# nanoDAP-mini.net
KiCad netlist of a schematic drawn in Altium Designer
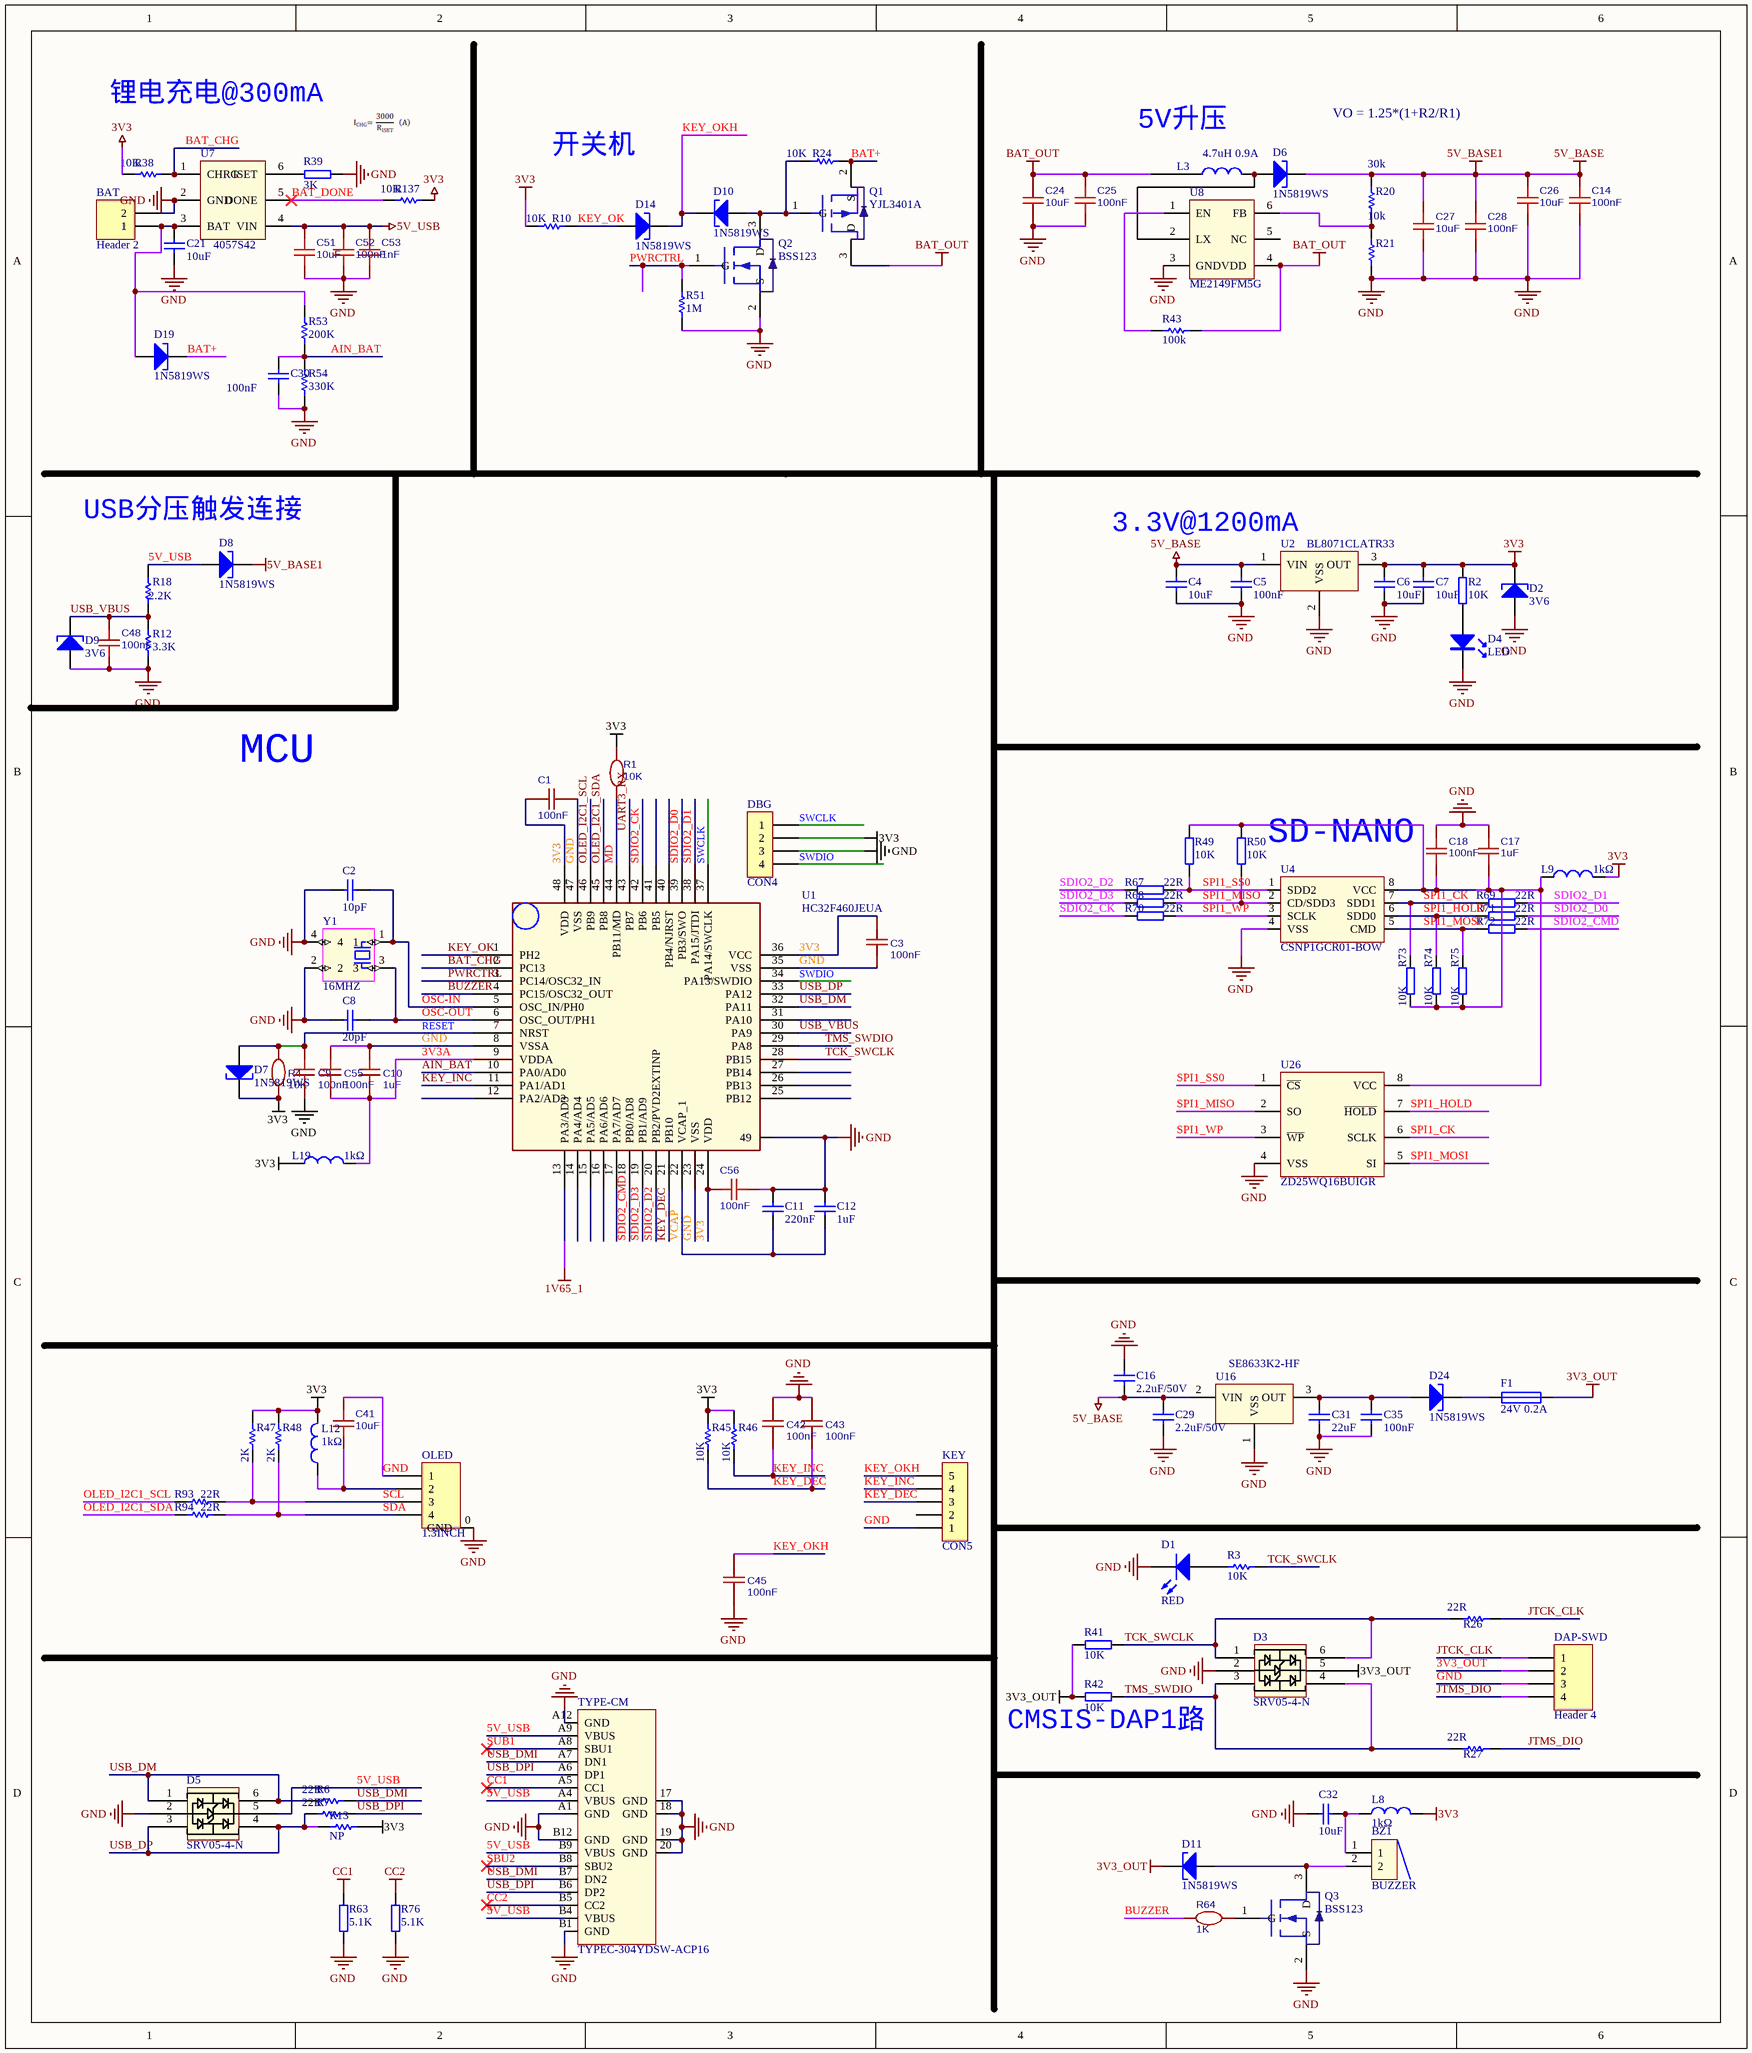
[diagram p0: nanoDAP-mini.SchDoc]

(export (version "E")
  (design (tool "Eeschema 10.0.6"))
  (components
    (comp (ref "BAT")
      (value "Header 2")
      (footprint "XH2.54-2P")
      (description "Header, 2-Pin")
      (fields (field (name "PUBLISHER") "Altium Limited"))
      (libsource (lib "Miscellaneous Connectors") (part "Header 2"))
    )
    (comp (ref "BZ1")
      (value "BUZZER")
      (footprint "BUZ-TH_BD9.0-P5.00-D0.6-FD")
      (libsource (lib "Schlib") (part "BUZZER"))
    )
    (comp (ref "C1")
      (value "100nF")
      (footprint "C0603")
      (libsource (lib "altium-import") (part "root_1_100nF_"))
    )
    (comp (ref "C2")
      (value "10pF")
      (footprint "C0603")
      (description "Capacitor")
      (fields (field (name "PUBLISHER") "Altium Limited"))
      (libsource (lib "Miscellaneous Devices") (part "Cap"))
    )
    (comp (ref "C3")
      (value "100nF")
      (footprint "C0603")
      (libsource (lib "altium-import") (part "root_0_100nF_"))
    )
    (comp (ref "C4")
      (value "10uF")
      (footprint "PcbLib:C0603")
      (description "电容")
      (libsource (lib "") (part "Cap2_1"))
    )
    (comp (ref "C5")
      (value "100nF")
      (footprint "PcbLib:C0603")
      (description "电容")
      (libsource (lib "") (part "Cap2_1"))
    )
    (comp (ref "C6")
      (value "10uF")
      (footprint "C0603")
      (description "电容")
      (libsource (lib "") (part "Cap2_1"))
    )
    (comp (ref "C7")
      (value "10uF")
      (footprint "C0603")
      (description "电容")
      (libsource (lib "Schlib") (part "Cap2"))
    )
    (comp (ref "C8")
      (value "20pF")
      (footprint "C0603")
      (description "Capacitor")
      (fields (field (name "PUBLISHER") "Altium Limited"))
      (libsource (lib "Miscellaneous Devices") (part "Cap"))
    )
    (comp (ref "C9")
      (value "100nF")
      (footprint "C0603")
      (libsource (lib "altium-import") (part "root_0_100nF_"))
    )
    (comp (ref "C10")
      (value "1uF")
      (footprint "C0603")
      (libsource (lib "altium-import") (part "root_0_100nF_"))
    )
    (comp (ref "C11")
      (value "220nF")
      (footprint "C0603")
      (description "Capacitor")
      (fields (field (name "PUBLISHER") "Altium Limited"))
      (libsource (lib "Miscellaneous Devices") (part "Cap"))
    )
    (comp (ref "C12")
      (value "1uF")
      (footprint "C0603")
      (description "Capacitor")
      (fields (field (name "PUBLISHER") "Altium Limited"))
      (libsource (lib "Miscellaneous Devices") (part "Cap"))
    )
    (comp (ref "C14")
      (value "100nF")
      (footprint "C0603")
      (libsource (lib "altium-import") (part "root_2_100nF_"))
    )
    (comp (ref "C16")
      (value "2.2uF/50V")
      (footprint "C0805")
      (description "电容")
      (libsource (lib "Schlib") (part "Cap2"))
    )
    (comp (ref "C17")
      (value "1uF")
      (footprint "C0603")
      (libsource (lib "altium-import") (part "root_0_100nF_"))
    )
    (comp (ref "C18")
      (value "100nF")
      (footprint "C0603")
      (libsource (lib "altium-import") (part "root_0_100nF_"))
    )
    (comp (ref "C21")
      (value "10uF")
      (footprint "C0603")
      (description "电容")
      (libsource (lib "Schlib") (part "Cap2"))
    )
    (comp (ref "C24")
      (value "10uF")
      (footprint "C0603")
      (libsource (lib "altium-import") (part "root_2_100nF_"))
    )
    (comp (ref "C25")
      (value "100nF")
      (footprint "C0603")
      (libsource (lib "altium-import") (part "root_2_100nF_"))
    )
    (comp (ref "C26")
      (value "10uF")
      (footprint "C0603")
      (libsource (lib "altium-import") (part "root_2_100nF_"))
    )
    (comp (ref "C27")
      (value "10uF")
      (footprint "C0603")
      (libsource (lib "altium-import") (part "root_2_100nF_"))
    )
    (comp (ref "C28")
      (value "100nF")
      (footprint "C0603")
      (libsource (lib "altium-import") (part "root_2_100nF_"))
    )
    (comp (ref "C29")
      (value "2.2uF/50V")
      (footprint "C0805")
      (description "电容")
      (libsource (lib "") (part "Cap2_1"))
    )
    (comp (ref "C30")
      (value "100nF")
      (footprint "C0603")
      (description "电容")
      (libsource (lib "Schlib") (part "Cap2"))
    )
    (comp (ref "C31")
      (value "22uF")
      (footprint "C0805")
      (description "电容")
      (libsource (lib "") (part "Cap2_1"))
    )
    (comp (ref "C32")
      (value "10uF")
      (footprint "C0603")
      (description "电容")
      (libsource (lib "Schlib") (part "Cap2"))
    )
    (comp (ref "C35")
      (value "100nF")
      (footprint "C0805")
      (description "电容")
      (libsource (lib "") (part "Cap2_1"))
    )
    (comp (ref "C41")
      (value "10uF")
      (footprint "C0603")
      (libsource (lib "altium-import") (part "root_2_100nF_"))
    )
    (comp (ref "C42")
      (value "100nF")
      (footprint "C0603")
      (libsource (lib "altium-import") (part "root_0_100nF_"))
    )
    (comp (ref "C43")
      (value "100nF")
      (footprint "C0603")
      (libsource (lib "altium-import") (part "root_0_100nF_"))
    )
    (comp (ref "C45")
      (value "100nF")
      (footprint "C0603")
      (libsource (lib "altium-import") (part "root_0_100nF_"))
    )
    (comp (ref "C48")
      (value "100nF")
      (footprint "C0603")
      (libsource (lib "altium-import") (part "root_0_100nF_"))
    )
    (comp (ref "C51")
      (value "10uF")
      (footprint "C0603")
      (libsource (lib "altium-import") (part "root_2_100nF_"))
    )
    (comp (ref "C52")
      (value "100nF")
      (footprint "C0603")
      (libsource (lib "altium-import") (part "root_2_100nF_"))
    )
    (comp (ref "C53")
      (value "1nF")
      (footprint "C0603")
      (libsource (lib "altium-import") (part "root_2_100nF_"))
    )
    (comp (ref "C55")
      (value "100nF")
      (footprint "C0603")
      (libsource (lib "altium-import") (part "root_0_100nF_"))
    )
    (comp (ref "C56")
      (value "100nF")
      (footprint "C0603")
      (libsource (lib "altium-import") (part "root_1_100nF_"))
    )
    (comp (ref "D1")
      (value "RED")
      (footprint "0603_LED")
      (description "Typical RED, GREEN, YELLOW, AMBER GaAs LED")
      (fields (field (name "PUBLISHER") "Altium Limited"))
      (libsource (lib "MYLIB") (part "D0603"))
    )
    (comp (ref "D2")
      (value "3V6")
      (footprint "LL-34")
      (description "稳压二极管")
      (fields (field (name "PUBLISHER") "Altium Limited"))
      (libsource (lib "Schlib") (part "Diode Zener"))
    )
    (comp (ref "D3") (value "SRV05-4-N") (footprint "SOT-23-6") (libsource (lib "Schlib") (part "ESD-USB")))
    (comp (ref "D4") (value "LED") (footprint "PcbLib:0603_LED") (libsource (lib "Schlib") (part "LED")))
    (comp (ref "D5") (value "SRV05-4-N") (footprint "SOT-23-6") (libsource (lib "Schlib") (part "ESD-USB")))
    (comp (ref "D6")
      (value "1N5819WS")
      (footprint "SOD-323")
      (description "稳压二极管")
      (fields (field (name "PUBLISHER") "Altium Limited"))
      (libsource (lib "Schlib") (part "Diode Zener"))
    )
    (comp (ref "D7")
      (value "1N5819WS")
      (footprint "SOD-323")
      (description "稳压二极管")
      (fields (field (name "PUBLISHER") "Altium Limited"))
      (libsource (lib "Schlib") (part "Diode Zener"))
    )
    (comp (ref "D8")
      (value "1N5819WS")
      (footprint "SOD-323")
      (description "稳压二极管")
      (fields (field (name "PUBLISHER") "Altium Limited"))
      (libsource (lib "Schlib") (part "Diode Zener"))
    )
    (comp (ref "D9")
      (value "3V6")
      (footprint "SOD-323")
      (description "稳压二极管")
      (fields (field (name "PUBLISHER") "Altium Limited"))
      (libsource (lib "Schlib") (part "Diode Zener"))
    )
    (comp (ref "D10")
      (value "1N5819WS")
      (footprint "SOD-323")
      (description "稳压二极管")
      (fields (field (name "PUBLISHER") "Altium Limited"))
      (libsource (lib "Schlib") (part "Diode Zener"))
    )
    (comp (ref "D11")
      (value "1N5819WS")
      (footprint "SOD-323")
      (description "稳压二极管")
      (fields (field (name "PUBLISHER") "Altium Limited"))
      (libsource (lib "Schlib") (part "Diode Zener"))
    )
    (comp (ref "D14")
      (value "1N5819WS")
      (footprint "SOD-323")
      (description "稳压二极管")
      (fields (field (name "PUBLISHER") "Altium Limited"))
      (libsource (lib "Schlib") (part "Diode Zener"))
    )
    (comp (ref "D19")
      (value "1N5819WS")
      (footprint "SOD-323")
      (description "稳压二极管")
      (fields (field (name "PUBLISHER") "Altium Limited"))
      (libsource (lib "Schlib") (part "Diode Zener"))
    )
    (comp (ref "D24")
      (value "1N5819WS")
      (footprint "SOD-323")
      (description "稳压二极管")
      (fields (field (name "PUBLISHER") "Altium Limited"))
      (libsource (lib "Schlib") (part "Diode Zener"))
    )
    (comp (ref "DAP-SWD")
      (value "Header 4")
      (footprint "XH2.54-4P")
      (description "Header, 4-Pin")
      (fields (field (name "PUBLISHER") "Altium Limited"))
      (libsource (lib "Miscellaneous Connectors") (part "Header 4"))
    )
    (comp (ref "DBG")
      (value "CON4")
      (footprint "PcbLib:HDR1X4-SWD")
      (description "连接器")
      (libsource (lib "Schlib") (part "CON4"))
    )
    (comp (ref "F1")
      (value "24V 0.2A")
      (footprint "R0805")
      (description "保险丝")
      (libsource (lib "Schlib") (part "FUSE"))
    )
    (comp (ref "KEY")
      (value "CON5")
      (footprint "HDR1X5")
      (description "连接器")
      (libsource (lib "Schlib") (part "CON5"))
    )
    (comp (ref "L3")
      (value "4.7uH 0.9A")
      (footprint "IND_3x3")
      (description "电感")
      (libsource (lib "Schlib") (part "Inductor"))
    )
    (comp (ref "L8")
      (value "1kΩ")
      (footprint "L0603")
      (description "电感")
      (libsource (lib "Schlib") (part "Inductor"))
    )
    (comp (ref "L9")
      (value "1kΩ")
      (footprint "L0603")
      (description "电感")
      (libsource (lib "Schlib") (part "Inductor"))
    )
    (comp (ref "L12")
      (value "1kΩ")
      (footprint "L0603")
      (description "电感")
      (libsource (lib "Schlib") (part "Inductor"))
    )
    (comp (ref "L19")
      (value "1kΩ")
      (footprint "L0603")
      (description "电感")
      (libsource (lib "Schlib") (part "Inductor"))
    )
    (comp (ref "OLED")
      (value "1.3INCH")
      (footprint "OLED-4p-1.3inch-i2c")
      (description "Header, 4-Pin")
      (fields (field (name "PUBLISHER") "Altium Limited"))
      (libsource (lib "") (part "Header 4_1"))
    )
    (comp (ref "Q1")
      (value "YJL3401A")
      (footprint "PcbLib:SOT-23(SOT-23-3)")
      (description "PMOS")
      (libsource (lib "Schlib") (part "PMOS"))
    )
    (comp (ref "Q2")
      (value "BSS123")
      (footprint "SOT-23(SOT-23-3)")
      (description "NMOS")
      (libsource (lib "Schlib") (part "NMOS"))
    )
    (comp (ref "Q3")
      (value "BSS123")
      (footprint "SOT-23(SOT-23-3)")
      (description "NMOS")
      (libsource (lib "Schlib") (part "NMOS"))
    )
    (comp (ref "R1") (value "10K") (footprint "R0603") (libsource (lib "altium-import") (part "root_3_10K_")))
    (comp (ref "R2")
      (value "10K")
      (footprint "R0603")
      (description "电阻")
      (libsource (lib "Schlib") (part "RES"))
    )
    (comp (ref "R3")
      (value "10K")
      (footprint "R0603")
      (description "Resistor")
      (fields (field (name "PUBLISHER") "Altium Limited"))
      (libsource (lib "MYLIB") (part "0603-1"))
    )
    (comp (ref "R4") (value "10K") (footprint "R0603") (libsource (lib "altium-import") (part "root_1_10K_")))
    (comp (ref "R6")
      (value "22R")
      (footprint "R0603")
      (description "Resistor")
      (fields (field (name "PUBLISHER") "Altium Limited"))
      (libsource (lib "MYLIB") (part "0603-1"))
    )
    (comp (ref "R7")
      (value "22R")
      (footprint "R0603")
      (description "Resistor")
      (fields (field (name "PUBLISHER") "Altium Limited"))
      (libsource (lib "MYLIB") (part "0603-1"))
    )
    (comp (ref "R10")
      (value "10K")
      (footprint "R0603")
      (description "Resistor")
      (fields (field (name "PUBLISHER") "Altium Limited"))
      (libsource (lib "MYLIB") (part "0603-1"))
    )
    (comp (ref "R12")
      (value "3.3K")
      (footprint "R0603")
      (description "Resistor")
      (fields (field (name "PUBLISHER") "Altium Limited"))
      (libsource (lib "MYLIB") (part "0603-1"))
    )
    (comp (ref "R13")
      (value "NP")
      (footprint "R0603")
      (description "Resistor")
      (fields (field (name "PUBLISHER") "Altium Limited"))
      (libsource (lib "MYLIB") (part "0603-1"))
    )
    (comp (ref "R18")
      (value "2.2K")
      (footprint "R0603")
      (description "Resistor")
      (fields (field (name "PUBLISHER") "Altium Limited"))
      (libsource (lib "MYLIB") (part "0603-1"))
    )
    (comp (ref "R20")
      (value "30k")
      (footprint "R0603")
      (description "Resistor")
      (fields (field (name "PUBLISHER") "Altium Limited"))
      (libsource (lib "MYLIB") (part "0603-1"))
    )
    (comp (ref "R21")
      (value "10k")
      (footprint "R0603")
      (description "Resistor")
      (fields (field (name "PUBLISHER") "Altium Limited"))
      (libsource (lib "MYLIB") (part "0603-1"))
    )
    (comp (ref "R24")
      (value "10K")
      (footprint "R0603")
      (description "Resistor")
      (fields (field (name "PUBLISHER") "Altium Limited"))
      (libsource (lib "MYLIB") (part "0603-1"))
    )
    (comp (ref "R26")
      (value "22R")
      (footprint "R0603")
      (description "Resistor")
      (fields (field (name "PUBLISHER") "Altium Limited"))
      (libsource (lib "MYLIB") (part "0603-1"))
    )
    (comp (ref "R27")
      (value "22R")
      (footprint "R0603")
      (description "Resistor")
      (fields (field (name "PUBLISHER") "Altium Limited"))
      (libsource (lib "MYLIB") (part "0603-1"))
    )
    (comp (ref "R38")
      (value "10K")
      (footprint "R0603")
      (description "Resistor")
      (fields (field (name "PUBLISHER") "Altium Limited"))
      (libsource (lib "MYLIB") (part "0603-1"))
    )
    (comp (ref "R39")
      (value "3K")
      (footprint "R0603")
      (description "电阻")
      (libsource (lib "Schlib") (part "RES"))
    )
    (comp (ref "R41")
      (value "10K")
      (footprint "R0603")
      (description "电阻")
      (libsource (lib "Schlib") (part "RES"))
    )
    (comp (ref "R42")
      (value "10K")
      (footprint "R0603")
      (description "电阻")
      (libsource (lib "Schlib") (part "RES"))
    )
    (comp (ref "R43")
      (value "100k")
      (footprint "R0603")
      (description "Resistor")
      (fields (field (name "PUBLISHER") "Altium Limited"))
      (libsource (lib "MYLIB") (part "0603-1"))
    )
    (comp (ref "R45")
      (value "10K")
      (footprint "R0603")
      (description "Resistor")
      (fields (field (name "PUBLISHER") "Altium Limited"))
      (libsource (lib "MYLIB") (part "0603-1"))
    )
    (comp (ref "R46")
      (value "10K")
      (footprint "R0603")
      (description "Resistor")
      (fields (field (name "PUBLISHER") "Altium Limited"))
      (libsource (lib "MYLIB") (part "0603-1"))
    )
    (comp (ref "R47")
      (value "2K")
      (footprint "R0603")
      (description "Resistor")
      (fields (field (name "PUBLISHER") "Altium Limited"))
      (libsource (lib "MYLIB") (part "0603-1"))
    )
    (comp (ref "R48")
      (value "2K")
      (footprint "R0603")
      (description "Resistor")
      (fields (field (name "PUBLISHER") "Altium Limited"))
      (libsource (lib "MYLIB") (part "0603-1"))
    )
    (comp (ref "R49")
      (value "10K")
      (footprint "R0603")
      (description "电阻")
      (libsource (lib "Schlib") (part "RES"))
    )
    (comp (ref "R50")
      (value "10K")
      (footprint "R0603")
      (description "电阻")
      (libsource (lib "Schlib") (part "RES"))
    )
    (comp (ref "R51")
      (value "1M")
      (footprint "R0603")
      (description "Resistor")
      (fields (field (name "PUBLISHER") "Altium Limited"))
      (libsource (lib "MYLIB") (part "0603-1"))
    )
    (comp (ref "R53")
      (value "200K")
      (footprint "R0603")
      (description "Resistor")
      (fields (field (name "PUBLISHER") "Altium Limited"))
      (libsource (lib "MYLIB") (part "0603-1"))
    )
    (comp (ref "R54")
      (value "330K")
      (footprint "R0603")
      (description "Resistor")
      (fields (field (name "PUBLISHER") "Altium Limited"))
      (libsource (lib "MYLIB") (part "0603-1"))
    )
    (comp (ref "R63")
      (value "5.1K")
      (footprint "R0603")
      (description "电阻")
      (libsource (lib "") (part "RES_1"))
    )
    (comp (ref "R64") (value "1K") (footprint "R0603") (libsource (lib "altium-import") (part "root_0_10K_")))
    (comp (ref "R67")
      (value "22R")
      (footprint "R0603")
      (description "电阻")
      (libsource (lib "Schlib") (part "RES"))
    )
    (comp (ref "R68")
      (value "22R")
      (footprint "R0603")
      (description "电阻")
      (libsource (lib "Schlib") (part "RES"))
    )
    (comp (ref "R69")
      (value "22R")
      (footprint "R0603")
      (description "电阻")
      (libsource (lib "Schlib") (part "RES"))
    )
    (comp (ref "R70")
      (value "22R")
      (footprint "R0603")
      (description "电阻")
      (libsource (lib "Schlib") (part "RES"))
    )
    (comp (ref "R71")
      (value "22R")
      (footprint "R0603")
      (description "电阻")
      (libsource (lib "Schlib") (part "RES"))
    )
    (comp (ref "R72")
      (value "22R")
      (footprint "R0603")
      (description "电阻")
      (libsource (lib "Schlib") (part "RES"))
    )
    (comp (ref "R73")
      (value "10K")
      (footprint "R0603")
      (description "电阻")
      (libsource (lib "Schlib") (part "RES"))
    )
    (comp (ref "R74")
      (value "10K")
      (footprint "R0603")
      (description "电阻")
      (libsource (lib "Schlib") (part "RES"))
    )
    (comp (ref "R75")
      (value "10K")
      (footprint "R0603")
      (description "电阻")
      (libsource (lib "Schlib") (part "RES"))
    )
    (comp (ref "R76")
      (value "5.1K")
      (footprint "R0603")
      (description "电阻")
      (libsource (lib "") (part "RES_1"))
    )
    (comp (ref "R93")
      (value "22R")
      (footprint "R0603")
      (description "Resistor")
      (fields (field (name "PUBLISHER") "Altium Limited"))
      (libsource (lib "MYLIB") (part "0603-1"))
    )
    (comp (ref "R94")
      (value "22R")
      (footprint "R0603")
      (description "Resistor")
      (fields (field (name "PUBLISHER") "Altium Limited"))
      (libsource (lib "MYLIB") (part "0603-1"))
    )
    (comp (ref "R137")
      (value "10K")
      (footprint "R0603")
      (description "Resistor")
      (fields (field (name "PUBLISHER") "Altium Limited"))
      (libsource (lib "MYLIB") (part "0603-1"))
    )
    (comp (ref "TYPE-CM")
      (value "TYPEC-304YDSW-ACP16")
      (footprint "USB-C-SMD_TYPEC-304YDSW-ACP16")
      (libsource (lib "Schlib") (part "USB-TYPE-C-母"))
    )
    (comp (ref "U1")
      (value "HC32F460JEUA")
      (footprint "QFN-48_5X5X035P")
      (libsource (lib "Schlib") (part "LQFP48"))
    )
    (comp (ref "U2") (value "BL8071CLATR33") (footprint "SOT-223") (libsource (lib "Schlib") (part "LDO")))
    (comp (ref "U4")
      (value "CSNP1GCR01-BOW")
      (footprint "LGA-8_L6.0-W8.0-P1.27-TL")
      (libsource (lib "Schlib") (part "SD-NAND-SMD"))
    )
    (comp (ref "U7") (value "4057S42") (footprint "SOT-23-6") (libsource (lib "Schlib") (part "IC_6")))
    (comp (ref "U8") (value "ME2149FM5G") (footprint "SOT-23-6") (libsource (lib "Schlib") (part "IC_6")))
    (comp (ref "U16") (value "SE8633K2-HF") (footprint "SOT-89&SOT-23") (libsource (lib "") (part "LDO_1")))
    (comp (ref "U26")
      (value "ZD25WQ16BUIGR")
      (footprint "USON-8_L3.0-W2.0-P0.50-BL-EP_ZD25XX")
      (libsource (lib "Schlib") (part "IC_8"))
    )
    (comp (ref "Y1")
      (value "16MHZ")
      (footprint "SMD-3225_4P")
      (libsource (lib "我的元件库") (part "crystal_smd_3225"))
    )
  )
  (nets
    (net (code "1") (name "/3V3A") (class "Default")
      (node (ref "C10") (pin "1") (pinfunction "1_1") (pintype "passive"))
      (node (ref "C55") (pin "1") (pinfunction "1_1") (pintype "passive"))
      (node (ref "L19") (pin "2") (pinfunction "2_2") (pintype "passive"))
      (node (ref "U1") (pin "9") (pinfunction "VDDA_9") (pintype "passive"))
    )
    (net (code "2") (name "/AIN_BAT") (class "Default")
      (node (ref "C30") (pin "1") (pinfunction "1_1") (pintype "passive"))
      (node (ref "R53") (pin "2") (pinfunction "2_2") (pintype "passive"))
      (node (ref "R54") (pin "2") (pinfunction "2_2") (pintype "passive"))
      (node (ref "U1") (pin "10") (pinfunction "PA0/AD0_10") (pintype "passive"))
    )
    (net (code "3") (name "/BAT+") (class "Default")
      (node (ref "D19") (pin "2") (pinfunction "K_2") (pintype "passive"))
      (node (ref "Q1") (pin "2") (pinfunction "S_2") (pintype "passive"))
      (node (ref "R24") (pin "1") (pinfunction "1_1") (pintype "passive"))
    )
    (net (code "4") (name "/BAT_CHG") (class "Default")
      (node (ref "R38") (pin "1") (pinfunction "1_1") (pintype "passive"))
      (node (ref "U1") (pin "2") (pinfunction "PC13_2") (pintype "passive"))
      (node (ref "U7") (pin "1") (pinfunction "CHRG_1") (pintype "passive"))
    )
    (net (code "5") (name "/BAT_DONE") (class "Default")
      (node (ref "R137") (pin "2") (pinfunction "2_2") (pintype "passive"))
      (node (ref "U7") (pin "5") (pinfunction "DONE_5") (pintype "passive"))
    )
    (net (code "6") (name "/BUZZER") (class "Default")
      (node (ref "R64") (pin "1") (pinfunction "1_1") (pintype "passive"))
      (node (ref "U1") (pin "4") (pinfunction "PC15/OSC32_OUT_4") (pintype "passive"))
    )
    (net (code "7") (name "/JTCK_CLK") (class "Default")
      (node (ref "DAP-SWD") (pin "1") (pinfunction "1_1") (pintype "passive"))
      (node (ref "R26") (pin "2") (pinfunction "2_2") (pintype "passive"))
    )
    (net (code "8") (name "/JTMS_DIO") (class "Default")
      (node (ref "DAP-SWD") (pin "4") (pinfunction "4_4") (pintype "passive"))
      (node (ref "R27") (pin "2") (pinfunction "2_2") (pintype "passive"))
    )
    (net (code "9") (name "/KEY_DEC") (class "Default")
      (node (ref "C43") (pin "1") (pinfunction "1_1") (pintype "passive"))
      (node (ref "KEY") (pin "3") (pinfunction "3_3") (pintype "passive"))
      (node (ref "R45") (pin "2") (pinfunction "2_2") (pintype "passive"))
      (node (ref "U1") (pin "21") (pinfunction "PB10_21") (pintype "passive"))
    )
    (net (code "10") (name "/KEY_INC") (class "Default")
      (node (ref "C42") (pin "1") (pinfunction "1_1") (pintype "passive"))
      (node (ref "KEY") (pin "4") (pinfunction "4_4") (pintype "passive"))
      (node (ref "R46") (pin "2") (pinfunction "2_2") (pintype "passive"))
      (node (ref "U1") (pin "11") (pinfunction "PA1/AD1_11") (pintype "passive"))
    )
    (net (code "11") (name "/KEY_OK") (class "Default")
      (node (ref "D14") (pin "1") (pinfunction "A_1") (pintype "passive"))
      (node (ref "R10") (pin "2") (pinfunction "2_2") (pintype "passive"))
      (node (ref "U1") (pin "1") (pinfunction "PH2_1") (pintype "passive"))
    )
    (net (code "12") (name "/KEY_OKH") (class "Default")
      (node (ref "C45") (pin "2") (pinfunction "2_2") (pintype "passive"))
      (node (ref "D10") (pin "2") (pinfunction "K_2") (pintype "passive"))
      (node (ref "D14") (pin "2") (pinfunction "K_2") (pintype "passive"))
      (node (ref "KEY") (pin "5") (pinfunction "5_5") (pintype "passive"))
    )
    (net (code "13") (name "/MD") (class "Default")
      (node (ref "R1") (pin "2") (pinfunction "2_2") (pintype "passive"))
      (node (ref "U1") (pin "44") (pinfunction "PB11/MD_44") (pintype "passive"))
    )
    (net (code "14") (name "/OLED_I2C1_SCL") (class "Default")
      (node (ref "R93") (pin "1") (pinfunction "1_1") (pintype "passive"))
      (node (ref "U1") (pin "46") (pinfunction "PB9_46") (pintype "passive"))
    )
    (net (code "15") (name "/OLED_I2C1_SDA") (class "Default")
      (node (ref "R94") (pin "1") (pinfunction "1_1") (pintype "passive"))
      (node (ref "U1") (pin "45") (pinfunction "PB8_45") (pintype "passive"))
    )
    (net (code "16") (name "/OSC-IN") (class "Default")
      (node (ref "C2") (pin "2") (pinfunction "2_2") (pintype "passive"))
      (node (ref "U1") (pin "5") (pinfunction "OSC_IN/PH0_5") (pintype "passive"))
      (node (ref "Y1") (pin "1") (pinfunction "1_1") (pintype "bidirectional"))
    )
    (net (code "17") (name "/OSC-OUT") (class "Default")
      (node (ref "C8") (pin "1") (pinfunction "1_1") (pintype "passive"))
      (node (ref "U1") (pin "6") (pinfunction "OSC_OUT/PH1_6") (pintype "passive"))
      (node (ref "Y1") (pin "3") (pinfunction "3_3") (pintype "bidirectional"))
    )
    (net (code "18") (name "/PWRCTRL") (class "Default")
      (node (ref "Q2") (pin "1") (pinfunction "G_1") (pintype "passive"))
      (node (ref "R51") (pin "1") (pinfunction "1_1") (pintype "passive"))
      (node (ref "U1") (pin "3") (pinfunction "PC14/OSC32_IN_3") (pintype "passive"))
    )
    (net (code "19") (name "/RESET") (class "Default")
      (node (ref "C9") (pin "2") (pinfunction "2_2") (pintype "passive"))
      (node (ref "D7") (pin "1") (pinfunction "A_1") (pintype "passive"))
      (node (ref "R4") (pin "2") (pinfunction "2_2") (pintype "passive"))
      (node (ref "U1") (pin "7") (pinfunction "NRST_7") (pintype "passive"))
    )
    (net (code "20") (name "/SBU2") (class "Default")
      (node (ref "TYPE-CM") (pin "B8") (pinfunction "SBU2_B8") (pintype "passive+no_connect"))
    )
    (net (code "21") (name "/SCL") (class "Default")
      (node (ref "OLED") (pin "3") (pinfunction "3_3") (pintype "passive"))
      (node (ref "R47") (pin "2") (pinfunction "2_2") (pintype "passive"))
      (node (ref "R93") (pin "2") (pinfunction "2_2") (pintype "passive"))
    )
    (net (code "22") (name "/SDA") (class "Default")
      (node (ref "OLED") (pin "4") (pinfunction "4_4") (pintype "passive"))
      (node (ref "R48") (pin "2") (pinfunction "2_2") (pintype "passive"))
      (node (ref "R94") (pin "2") (pinfunction "2_2") (pintype "passive"))
    )
    (net (code "23") (name "/SDIO2_CK") (class "Default")
      (node (ref "R70") (pin "2") (pinfunction "2_2") (pintype "passive"))
      (node (ref "U1") (pin "42") (pinfunction "PB6_42") (pintype "passive"))
    )
    (net (code "24") (name "/SDIO2_CMD") (class "Default")
      (node (ref "R72") (pin "1") (pinfunction "1_1") (pintype "passive"))
      (node (ref "U1") (pin "18") (pinfunction "PB0/AD8_18") (pintype "passive"))
    )
    (net (code "25") (name "/SDIO2_D0") (class "Default")
      (node (ref "R71") (pin "1") (pinfunction "1_1") (pintype "passive"))
      (node (ref "U1") (pin "39") (pinfunction "PB3/SWO_39") (pintype "passive"))
    )
    (net (code "26") (name "/SDIO2_D1") (class "Default")
      (node (ref "R69") (pin "1") (pinfunction "1_1") (pintype "passive"))
      (node (ref "U1") (pin "38") (pinfunction "PA15/JTDI_38") (pintype "passive"))
    )
    (net (code "27") (name "/SDIO2_D2") (class "Default")
      (node (ref "R67") (pin "2") (pinfunction "2_2") (pintype "passive"))
      (node (ref "U1") (pin "20") (pinfunction "PB2/PVD2EXTINP_20") (pintype "passive"))
    )
    (net (code "28") (name "/SDIO2_D3") (class "Default")
      (node (ref "R68") (pin "2") (pinfunction "2_2") (pintype "passive"))
      (node (ref "U1") (pin "19") (pinfunction "PB1/AD9_19") (pintype "passive"))
    )
    (net (code "29") (name "/SPI1_CK") (class "Default")
      (node (ref "R69") (pin "2") (pinfunction "2_2") (pintype "passive"))
      (node (ref "R73") (pin "1") (pinfunction "1_1") (pintype "passive"))
      (node (ref "U26") (pin "6") (pinfunction "SCLK_6") (pintype "passive"))
      (node (ref "U4") (pin "7") (pinfunction "SDD1_7") (pintype "passive"))
    )
    (net (code "30") (name "/SPI1_HOLD") (class "Default")
      (node (ref "R71") (pin "2") (pinfunction "2_2") (pintype "passive"))
      (node (ref "R74") (pin "1") (pinfunction "1_1") (pintype "passive"))
      (node (ref "U26") (pin "7") (pinfunction "~{HOLD}_7") (pintype "passive"))
      (node (ref "U4") (pin "6") (pinfunction "SDD0_6") (pintype "passive"))
    )
    (net (code "31") (name "/SPI1_MISO") (class "Default")
      (node (ref "R50") (pin "1") (pinfunction "1_1") (pintype "passive"))
      (node (ref "R68") (pin "1") (pinfunction "1_1") (pintype "passive"))
      (node (ref "U26") (pin "2") (pinfunction "SO_2") (pintype "passive"))
      (node (ref "U4") (pin "2") (pinfunction "CD/SDD3_2") (pintype "passive"))
    )
    (net (code "32") (name "/SPI1_MOSI") (class "Default")
      (node (ref "R72") (pin "2") (pinfunction "2_2") (pintype "passive"))
      (node (ref "R75") (pin "1") (pinfunction "1_1") (pintype "passive"))
      (node (ref "U26") (pin "5") (pinfunction "SI_5") (pintype "passive"))
      (node (ref "U4") (pin "5") (pinfunction "CMD_5") (pintype "passive"))
    )
    (net (code "33") (name "/SPI1_SS0") (class "Default")
      (node (ref "R49") (pin "1") (pinfunction "1_1") (pintype "passive"))
      (node (ref "R67") (pin "1") (pinfunction "1_1") (pintype "passive"))
      (node (ref "U26") (pin "1") (pinfunction "~{CS}_1") (pintype "passive"))
      (node (ref "U4") (pin "1") (pinfunction "SDD2_1") (pintype "passive"))
    )
    (net (code "34") (name "/SPI1_WP") (class "Default")
      (node (ref "R70") (pin "1") (pinfunction "1_1") (pintype "passive"))
      (node (ref "U26") (pin "3") (pinfunction "~{WP}_3") (pintype "passive"))
      (node (ref "U4") (pin "3") (pinfunction "SCLK_3") (pintype "passive"))
    )
    (net (code "35") (name "/SUB1") (class "Default")
      (node (ref "TYPE-CM") (pin "A8") (pinfunction "SBU1_A8") (pintype "passive+no_connect"))
    )
    (net (code "36") (name "/SWCLK") (class "Default")
      (node (ref "DBG") (pin "1") (pinfunction "1_1") (pintype "passive"))
      (node (ref "U1") (pin "37") (pinfunction "PA14/SWCLK_37") (pintype "passive"))
    )
    (net (code "37") (name "/SWDIO") (class "Default")
      (node (ref "DBG") (pin "4") (pinfunction "4_4") (pintype "passive"))
      (node (ref "U1") (pin "34") (pinfunction "PA13/SWDIO_34") (pintype "passive"))
    )
    (net (code "38") (name "/TCK_SWCLK") (class "Default")
      (node (ref "D3") (pin "1") (pintype "passive"))
      (node (ref "D3") (pin "6") (pintype "passive"))
      (node (ref "R26") (pin "1") (pinfunction "1_1") (pintype "passive"))
      (node (ref "R3") (pin "2") (pinfunction "2_2") (pintype "passive"))
      (node (ref "R41") (pin "2") (pinfunction "2_2") (pintype "passive"))
      (node (ref "U1") (pin "28") (pinfunction "PB15_28") (pintype "passive"))
    )
    (net (code "39") (name "/TMS_SWDIO") (class "Default")
      (node (ref "D3") (pin "3") (pintype "passive"))
      (node (ref "D3") (pin "4") (pintype "passive"))
      (node (ref "R27") (pin "1") (pinfunction "1_1") (pintype "passive"))
      (node (ref "R42") (pin "2") (pinfunction "2_2") (pintype "passive"))
      (node (ref "U1") (pin "29") (pinfunction "PA8_29") (pintype "passive"))
    )
    (net (code "40") (name "/UART3_RX") (class "Default")
      (node (ref "U1") (pin "43") (pinfunction "PB7_43") (pintype "passive"))
    )
    (net (code "41") (name "/USB_DM") (class "Default")
      (node (ref "D5") (pin "1") (pintype "passive"))
      (node (ref "D5") (pin "6") (pintype "passive"))
      (node (ref "R6") (pin "1") (pinfunction "1_1") (pintype "passive"))
      (node (ref "U1") (pin "32") (pinfunction "PA11_32") (pintype "passive"))
    )
    (net (code "42") (name "/USB_DMI") (class "Default")
      (node (ref "R6") (pin "2") (pinfunction "2_2") (pintype "passive"))
      (node (ref "TYPE-CM") (pin "A7") (pinfunction "DN1_A7") (pintype "passive"))
      (node (ref "TYPE-CM") (pin "B7") (pinfunction "DN2_B7") (pintype "passive"))
    )
    (net (code "43") (name "/USB_DP") (class "Default")
      (node (ref "D5") (pin "3") (pintype "passive"))
      (node (ref "D5") (pin "4") (pintype "passive"))
      (node (ref "R13") (pin "1") (pinfunction "1_1") (pintype "passive"))
      (node (ref "R7") (pin "1") (pinfunction "1_1") (pintype "passive"))
      (node (ref "U1") (pin "33") (pinfunction "PA12_33") (pintype "passive"))
    )
    (net (code "44") (name "/USB_DPI") (class "Default")
      (node (ref "R7") (pin "2") (pinfunction "2_2") (pintype "passive"))
      (node (ref "TYPE-CM") (pin "A6") (pinfunction "DP1_A6") (pintype "passive"))
      (node (ref "TYPE-CM") (pin "B6") (pinfunction "DP2_B6") (pintype "passive"))
    )
    (net (code "45") (name "/USB_VBUS") (class "Default")
      (node (ref "C48") (pin "2") (pinfunction "2_2") (pintype "passive"))
      (node (ref "D9") (pin "2") (pinfunction "K_2") (pintype "passive"))
      (node (ref "R12") (pin "1") (pinfunction "1_1") (pintype "passive"))
      (node (ref "R18") (pin "2") (pinfunction "2_2") (pintype "passive"))
      (node (ref "U1") (pin "30") (pinfunction "PA9_30") (pintype "passive"))
    )
    (net (code "46") (name "/VCAP") (class "Default")
      (node (ref "C11") (pin "2") (pinfunction "2_2") (pintype "passive"))
      (node (ref "C12") (pin "2") (pinfunction "2_2") (pintype "passive"))
      (node (ref "U1") (pin "22") (pinfunction "VCAP_1_22") (pintype "passive"))
    )
    (net (code "47") (name "1V65_1") (class "Default")
      (node (ref "U1") (pin "13") (pinfunction "PA3/AD3_13") (pintype "passive"))
    )
    (net (code "48") (name "3V3") (class "Default")
      (node (ref "C1") (pin "2") (pinfunction "2_2") (pintype "passive"))
      (node (ref "C3") (pin "2") (pinfunction "2_2") (pintype "passive"))
      (node (ref "C56") (pin "2") (pinfunction "2_2") (pintype "passive"))
      (node (ref "C6") (pin "1") (pinfunction "1_1") (pintype "passive"))
      (node (ref "C7") (pin "1") (pinfunction "1_1") (pintype "passive"))
      (node (ref "D2") (pin "2") (pinfunction "K_2") (pintype "passive"))
      (node (ref "D7") (pin "2") (pinfunction "K_2") (pintype "passive"))
      (node (ref "DBG") (pin "2") (pinfunction "2_2") (pintype "passive"))
      (node (ref "L12") (pin "2") (pinfunction "2_2") (pintype "passive"))
      (node (ref "L19") (pin "1") (pinfunction "1_1") (pintype "passive"))
      (node (ref "L8") (pin "2") (pinfunction "2_2") (pintype "passive"))
      (node (ref "L9") (pin "2") (pinfunction "2_2") (pintype "passive"))
      (node (ref "R1") (pin "1") (pinfunction "1_1") (pintype "passive"))
      (node (ref "R10") (pin "1") (pinfunction "1_1") (pintype "passive"))
      (node (ref "R13") (pin "2") (pinfunction "2_2") (pintype "passive"))
      (node (ref "R137") (pin "1") (pinfunction "1_1") (pintype "passive"))
      (node (ref "R2") (pin "1") (pinfunction "1_1") (pintype "passive"))
      (node (ref "R38") (pin "2") (pinfunction "2_2") (pintype "passive"))
      (node (ref "R4") (pin "1") (pinfunction "1_1") (pintype "passive"))
      (node (ref "R45") (pin "1") (pinfunction "1_1") (pintype "passive"))
      (node (ref "R46") (pin "1") (pinfunction "1_1") (pintype "passive"))
      (node (ref "R47") (pin "1") (pinfunction "1_1") (pintype "passive"))
      (node (ref "R48") (pin "1") (pinfunction "1_1") (pintype "passive"))
      (node (ref "U1") (pin "24") (pinfunction "VDD_24") (pintype "passive"))
      (node (ref "U1") (pin "36") (pinfunction "VCC_36") (pintype "passive"))
      (node (ref "U1") (pin "48") (pinfunction "VDD_48") (pintype "passive"))
      (node (ref "U2") (pin "3") (pinfunction "OUT_3") (pintype "passive"))
    )
    (net (code "49") (name "3V3_OUT") (class "Default")
      (node (ref "D11") (pin "2") (pinfunction "K_2") (pintype "passive"))
      (node (ref "D3") (pin "5") (pintype "passive"))
      (node (ref "DAP-SWD") (pin "2") (pinfunction "2_2") (pintype "passive"))
      (node (ref "F1") (pin "2") (pinfunction "2_2") (pintype "passive"))
      (node (ref "R41") (pin "1") (pinfunction "1_1") (pintype "passive"))
      (node (ref "R42") (pin "1") (pinfunction "1_1") (pintype "passive"))
    )
    (net (code "50") (name "5V_BASE") (class "Default")
      (node (ref "C14") (pin "1") (pinfunction "1_1") (pintype "passive"))
      (node (ref "C16") (pin "1") (pinfunction "1_1") (pintype "passive"))
      (node (ref "C26") (pin "1") (pinfunction "1_1") (pintype "passive"))
      (node (ref "C27") (pin "1") (pinfunction "1_1") (pintype "passive"))
      (node (ref "C28") (pin "1") (pinfunction "1_1") (pintype "passive"))
      (node (ref "C29") (pin "1") (pinfunction "1_1") (pintype "passive"))
      (node (ref "C4") (pin "1") (pinfunction "1_1") (pintype "passive"))
      (node (ref "C5") (pin "1") (pinfunction "1_1") (pintype "passive"))
      (node (ref "D6") (pin "2") (pinfunction "K_2") (pintype "passive"))
      (node (ref "D8") (pin "2") (pinfunction "K_2") (pintype "passive"))
      (node (ref "R20") (pin "2") (pinfunction "2_2") (pintype "passive"))
      (node (ref "U16") (pin "2") (pinfunction "VIN_2") (pintype "passive"))
      (node (ref "U2") (pin "1") (pinfunction "VIN_1") (pintype "passive"))
    )
    (net (code "51") (name "5V_USB") (class "Default")
      (node (ref "C51") (pin "1") (pinfunction "1_1") (pintype "passive"))
      (node (ref "C52") (pin "1") (pinfunction "1_1") (pintype "passive"))
      (node (ref "C53") (pin "1") (pinfunction "1_1") (pintype "passive"))
      (node (ref "D5") (pin "5") (pintype "passive"))
      (node (ref "D8") (pin "1") (pinfunction "A_1") (pintype "passive"))
      (node (ref "R18") (pin "1") (pinfunction "1_1") (pintype "passive"))
      (node (ref "TYPE-CM") (pin "A4") (pinfunction "VBUS_A4") (pintype "passive"))
      (node (ref "TYPE-CM") (pin "A9") (pinfunction "VBUS_A9") (pintype "passive"))
      (node (ref "TYPE-CM") (pin "B4") (pinfunction "VBUS_B4") (pintype "passive"))
      (node (ref "TYPE-CM") (pin "B9") (pinfunction "VBUS_B9") (pintype "passive"))
      (node (ref "U7") (pin "4") (pinfunction "VIN_4") (pintype "passive"))
    )
    (net (code "52") (name "BAT_OUT") (class "Default")
      (node (ref "C24") (pin "1") (pinfunction "1_1") (pintype "passive"))
      (node (ref "C25") (pin "1") (pinfunction "1_1") (pintype "passive"))
      (node (ref "L3") (pin "1") (pinfunction "1_1") (pintype "passive"))
      (node (ref "Q1") (pin "3") (pinfunction "D_3") (pintype "passive"))
      (node (ref "R43") (pin "2") (pinfunction "2_2") (pintype "passive"))
      (node (ref "U8") (pin "4") (pinfunction "VIN_4") (pintype "passive"))
    )
    (net (code "53") (name "CC1") (class "Default")
      (node (ref "R63") (pin "2") (pinfunction "2_2") (pintype "passive"))
      (node (ref "TYPE-CM") (pin "A5") (pinfunction "CC1_A5") (pintype "passive"))
    )
    (net (code "54") (name "CC2") (class "Default")
      (node (ref "R76") (pin "2") (pinfunction "2_2") (pintype "passive"))
      (node (ref "TYPE-CM") (pin "B5") (pinfunction "CC2_B5") (pintype "passive"))
    )
    (net (code "55") (name "GND") (class "Default")
      (node (ref "BAT") (pin "2") (pinfunction "2_2") (pintype "passive"))
      (node (ref "C1") (pin "1") (pinfunction "1_1") (pintype "passive"))
      (node (ref "C10") (pin "2") (pinfunction "2_2") (pintype "passive"))
      (node (ref "C11") (pin "1") (pinfunction "1_1") (pintype "passive"))
      (node (ref "C12") (pin "1") (pinfunction "1_1") (pintype "passive"))
      (node (ref "C14") (pin "2") (pinfunction "2_2") (pintype "passive"))
      (node (ref "C16") (pin "2") (pinfunction "2_2") (pintype "passive"))
      (node (ref "C17") (pin "2") (pinfunction "2_2") (pintype "passive"))
      (node (ref "C18") (pin "2") (pinfunction "2_2") (pintype "passive"))
      (node (ref "C2") (pin "1") (pinfunction "1_1") (pintype "passive"))
      (node (ref "C21") (pin "2") (pinfunction "2_2") (pintype "passive"))
      (node (ref "C24") (pin "2") (pinfunction "2_2") (pintype "passive"))
      (node (ref "C25") (pin "2") (pinfunction "2_2") (pintype "passive"))
      (node (ref "C26") (pin "2") (pinfunction "2_2") (pintype "passive"))
      (node (ref "C27") (pin "2") (pinfunction "2_2") (pintype "passive"))
      (node (ref "C28") (pin "2") (pinfunction "2_2") (pintype "passive"))
      (node (ref "C29") (pin "2") (pinfunction "2_2") (pintype "passive"))
      (node (ref "C3") (pin "1") (pinfunction "1_1") (pintype "passive"))
      (node (ref "C30") (pin "2") (pinfunction "2_2") (pintype "passive"))
      (node (ref "C31") (pin "2") (pinfunction "2_2") (pintype "passive"))
      (node (ref "C32") (pin "1") (pinfunction "1_1") (pintype "passive"))
      (node (ref "C35") (pin "2") (pinfunction "2_2") (pintype "passive"))
      (node (ref "C4") (pin "2") (pinfunction "2_2") (pintype "passive"))
      (node (ref "C41") (pin "1") (pinfunction "1_1") (pintype "passive"))
      (node (ref "C42") (pin "2") (pinfunction "2_2") (pintype "passive"))
      (node (ref "C43") (pin "2") (pinfunction "2_2") (pintype "passive"))
      (node (ref "C45") (pin "1") (pinfunction "1_1") (pintype "passive"))
      (node (ref "C48") (pin "1") (pinfunction "1_1") (pintype "passive"))
      (node (ref "C5") (pin "2") (pinfunction "2_2") (pintype "passive"))
      (node (ref "C51") (pin "2") (pinfunction "2_2") (pintype "passive"))
      (node (ref "C52") (pin "2") (pinfunction "2_2") (pintype "passive"))
      (node (ref "C53") (pin "2") (pinfunction "2_2") (pintype "passive"))
      (node (ref "C55") (pin "2") (pinfunction "2_2") (pintype "passive"))
      (node (ref "C56") (pin "1") (pinfunction "1_1") (pintype "passive"))
      (node (ref "C6") (pin "2") (pinfunction "2_2") (pintype "passive"))
      (node (ref "C7") (pin "2") (pinfunction "2_2") (pintype "passive"))
      (node (ref "C8") (pin "2") (pinfunction "2_2") (pintype "passive"))
      (node (ref "C9") (pin "1") (pinfunction "1_1") (pintype "passive"))
      (node (ref "D1") (pin "2") (pinfunction "K_2") (pintype "passive"))
      (node (ref "D2") (pin "1") (pinfunction "A_1") (pintype "passive"))
      (node (ref "D3") (pin "2") (pintype "passive"))
      (node (ref "D4") (pin "2") (pinfunction "2_2") (pintype "passive"))
      (node (ref "D5") (pin "2") (pintype "passive"))
      (node (ref "D9") (pin "1") (pinfunction "A_1") (pintype "passive"))
      (node (ref "DAP-SWD") (pin "3") (pinfunction "3_3") (pintype "passive"))
      (node (ref "DBG") (pin "3") (pinfunction "3_3") (pintype "passive"))
      (node (ref "KEY") (pin "1") (pinfunction "1_1") (pintype "passive"))
      (node (ref "OLED") (pin "0") (pinfunction "GND_0") (pintype "passive"))
      (node (ref "OLED") (pin "1") (pinfunction "1_1") (pintype "passive"))
      (node (ref "Q2") (pin "2") (pinfunction "S_2") (pintype "passive"))
      (node (ref "Q3") (pin "2") (pinfunction "S_2") (pintype "passive"))
      (node (ref "R12") (pin "2") (pinfunction "2_2") (pintype "passive"))
      (node (ref "R21") (pin "2") (pinfunction "2_2") (pintype "passive"))
      (node (ref "R39") (pin "2") (pinfunction "2_2") (pintype "passive"))
      (node (ref "R51") (pin "2") (pinfunction "2_2") (pintype "passive"))
      (node (ref "R54") (pin "1") (pinfunction "1_1") (pintype "passive"))
      (node (ref "R63") (pin "1") (pinfunction "1_1") (pintype "passive"))
      (node (ref "R76") (pin "1") (pinfunction "1_1") (pintype "passive"))
      (node (ref "TYPE-CM") (pin "17") (pinfunction "GND_17") (pintype "passive"))
      (node (ref "TYPE-CM") (pin "18") (pinfunction "GND_18") (pintype "passive"))
      (node (ref "TYPE-CM") (pin "19") (pinfunction "GND_19") (pintype "passive"))
      (node (ref "TYPE-CM") (pin "20") (pinfunction "GND_20") (pintype "passive"))
      (node (ref "TYPE-CM") (pin "A1") (pinfunction "GND_A1") (pintype "passive"))
      (node (ref "TYPE-CM") (pin "A12") (pinfunction "GND_A12") (pintype "passive"))
      (node (ref "TYPE-CM") (pin "B1") (pinfunction "GND_B1") (pintype "passive"))
      (node (ref "TYPE-CM") (pin "B12") (pinfunction "GND_B12") (pintype "passive"))
      (node (ref "U1") (pin "23") (pinfunction "VSS_23") (pintype "passive"))
      (node (ref "U1") (pin "35") (pinfunction "VSS_35") (pintype "passive"))
      (node (ref "U1") (pin "47") (pinfunction "VSS_47") (pintype "passive"))
      (node (ref "U1") (pin "49") (pinfunction "49_49") (pintype "passive"))
      (node (ref "U1") (pin "8") (pinfunction "VSSA_8") (pintype "passive"))
      (node (ref "U16") (pin "1") (pinfunction "VSS_1") (pintype "passive"))
      (node (ref "U2") (pin "2") (pinfunction "VSS_2") (pintype "passive"))
      (node (ref "U26") (pin "4") (pinfunction "VSS_4") (pintype "passive"))
      (node (ref "U4") (pin "4") (pinfunction "VSS_4") (pintype "passive"))
      (node (ref "U7") (pin "2") (pinfunction "GND_2") (pintype "passive"))
      (node (ref "U8") (pin "3") (pinfunction "BAT_3") (pintype "passive"))
      (node (ref "Y1") (pin "2") (pinfunction "2_2") (pintype "bidirectional"))
      (node (ref "Y1") (pin "4") (pinfunction "4_4") (pintype "bidirectional"))
    )
    (net (code "56") (name "Net-(BZ1-Pad1)") (class "Default")
      (node (ref "BZ1") (pin "1") (pinfunction "1_1") (pintype "passive"))
      (node (ref "C32") (pin "2") (pinfunction "2_2") (pintype "passive"))
      (node (ref "L8") (pin "1") (pinfunction "1_1") (pintype "passive"))
    )
    (net (code "57") (name "Net-(C41-Pad2)") (class "Default")
      (node (ref "C41") (pin "2") (pinfunction "2_2") (pintype "passive"))
      (node (ref "L12") (pin "1") (pinfunction "1_1") (pintype "passive"))
      (node (ref "OLED") (pin "2") (pinfunction "2_2") (pintype "passive"))
    )
    (net (code "58") (name "Net-(D1-A)") (class "Default")
      (node (ref "D1") (pin "1") (pinfunction "A_1") (pintype "passive"))
      (node (ref "R3") (pin "1") (pinfunction "1_1") (pintype "passive"))
    )
    (net (code "59") (name "Net-(D4-Pad1)") (class "Default")
      (node (ref "D4") (pin "1") (pinfunction "1_1") (pintype "passive"))
      (node (ref "R2") (pin "2") (pinfunction "2_2") (pintype "passive"))
    )
    (net (code "60") (name "Net-(D6-A)") (class "Default")
      (node (ref "D6") (pin "1") (pinfunction "A_1") (pintype "passive"))
      (node (ref "L3") (pin "2") (pinfunction "2_2") (pintype "passive"))
      (node (ref "U8") (pin "2") (pinfunction "GND_2") (pintype "passive"))
    )
    (net (code "61") (name "Net-(D10-A)") (class "Default")
      (node (ref "D10") (pin "1") (pinfunction "A_1") (pintype "passive"))
      (node (ref "Q1") (pin "1") (pinfunction "G_1") (pintype "passive"))
      (node (ref "Q2") (pin "3") (pinfunction "D_3") (pintype "passive"))
      (node (ref "R24") (pin "2") (pinfunction "2_2") (pintype "passive"))
    )
    (net (code "62") (name "Net-(D11-A)") (class "Default")
      (node (ref "BZ1") (pin "2") (pinfunction "2_2") (pintype "passive"))
      (node (ref "D11") (pin "1") (pinfunction "A_1") (pintype "passive"))
      (node (ref "Q3") (pin "3") (pinfunction "D_3") (pintype "passive"))
    )
    (net (code "63") (name "Net-(D19-A)") (class "Default")
      (node (ref "BAT") (pin "1") (pinfunction "1_1") (pintype "passive"))
      (node (ref "C21") (pin "1") (pinfunction "1_1") (pintype "passive"))
      (node (ref "D19") (pin "1") (pinfunction "A_1") (pintype "passive"))
      (node (ref "R53") (pin "1") (pinfunction "1_1") (pintype "passive"))
      (node (ref "U7") (pin "3") (pinfunction "BAT_3") (pintype "passive"))
    )
    (net (code "64") (name "Net-(D24-A)") (class "Default")
      (node (ref "C31") (pin "1") (pinfunction "1_1") (pintype "passive"))
      (node (ref "C35") (pin "1") (pinfunction "1_1") (pintype "passive"))
      (node (ref "D24") (pin "1") (pinfunction "A_1") (pintype "passive"))
      (node (ref "U16") (pin "3") (pinfunction "OUT_3") (pintype "passive"))
    )
    (net (code "65") (name "Net-(D24-K)") (class "Default")
      (node (ref "D24") (pin "2") (pinfunction "K_2") (pintype "passive"))
      (node (ref "F1") (pin "1") (pinfunction "1_1") (pintype "passive"))
    )
    (net (code "66") (name "Net-(Q3-G)") (class "Default")
      (node (ref "Q3") (pin "1") (pinfunction "G_1") (pintype "passive"))
      (node (ref "R64") (pin "2") (pinfunction "2_2") (pintype "passive"))
    )
    (net (code "67") (name "Net-(U7-ISET)") (class "Default")
      (node (ref "R39") (pin "1") (pinfunction "1_1") (pintype "passive"))
      (node (ref "U7") (pin "6") (pinfunction "ISET_6") (pintype "passive"))
    )
    (net (code "68") (name "Net-(U8-CHRG)") (class "Default")
      (node (ref "R43") (pin "1") (pinfunction "1_1") (pintype "passive"))
      (node (ref "U8") (pin "1") (pinfunction "CHRG_1") (pintype "passive"))
    )
    (net (code "69") (name "Net-(U8-ISET)") (class "Default")
      (node (ref "R20") (pin "1") (pinfunction "1_1") (pintype "passive"))
      (node (ref "R21") (pin "1") (pinfunction "1_1") (pintype "passive"))
      (node (ref "U8") (pin "6") (pinfunction "ISET_6") (pintype "passive"))
    )
    (net (code "70") (name "Net-(U26-VCC)") (class "Default")
      (node (ref "C17") (pin "1") (pinfunction "1_1") (pintype "passive"))
      (node (ref "C18") (pin "1") (pinfunction "1_1") (pintype "passive"))
      (node (ref "L9") (pin "1") (pinfunction "1_1") (pintype "passive"))
      (node (ref "R49") (pin "2") (pinfunction "2_2") (pintype "passive"))
      (node (ref "R50") (pin "2") (pinfunction "2_2") (pintype "passive"))
      (node (ref "R73") (pin "2") (pinfunction "2_2") (pintype "passive"))
      (node (ref "R74") (pin "2") (pinfunction "2_2") (pintype "passive"))
      (node (ref "R75") (pin "2") (pinfunction "2_2") (pintype "passive"))
      (node (ref "U26") (pin "8") (pinfunction "VCC_8") (pintype "passive"))
      (node (ref "U4") (pin "8") (pinfunction "VCC_8") (pintype "passive"))
    )
    (net (code "71") (name "unconnected-(KEY-Pad2)") (class "Default")
      (node (ref "KEY") (pin "2") (pinfunction "2_2") (pintype "passive"))
    )
    (net (code "72") (name "unconnected-(U1-PA2{slash}AD2-Pad12)") (class "Default")
      (node (ref "U1") (pin "12") (pinfunction "PA2/AD2_12") (pintype "passive"))
    )
    (net (code "73") (name "unconnected-(U1-PA4{slash}AD4-Pad14)") (class "Default")
      (node (ref "U1") (pin "14") (pinfunction "PA4/AD4_14") (pintype "passive"))
    )
    (net (code "74") (name "unconnected-(U1-PA5{slash}AD5-Pad15)") (class "Default")
      (node (ref "U1") (pin "15") (pinfunction "PA5/AD5_15") (pintype "passive"))
    )
    (net (code "75") (name "unconnected-(U1-PA6{slash}AD6-Pad16)") (class "Default")
      (node (ref "U1") (pin "16") (pinfunction "PA6/AD6_16") (pintype "passive"))
    )
    (net (code "76") (name "unconnected-(U1-PA7{slash}AD7-Pad17)") (class "Default")
      (node (ref "U1") (pin "17") (pinfunction "PA7/AD7_17") (pintype "passive"))
    )
    (net (code "77") (name "unconnected-(U1-PA10-Pad31)") (class "Default")
      (node (ref "U1") (pin "31") (pinfunction "PA10_31") (pintype "passive"))
    )
    (net (code "78") (name "unconnected-(U1-PB4{slash}NJRST-Pad40)") (class "Default")
      (node (ref "U1") (pin "40") (pinfunction "PB4/NJRST_40") (pintype "passive"))
    )
    (net (code "79") (name "unconnected-(U1-PB5-Pad41)") (class "Default")
      (node (ref "U1") (pin "41") (pinfunction "PB5_41") (pintype "passive"))
    )
    (net (code "80") (name "unconnected-(U1-PB12-Pad25)") (class "Default")
      (node (ref "U1") (pin "25") (pinfunction "PB12_25") (pintype "passive"))
    )
    (net (code "81") (name "unconnected-(U1-PB13-Pad26)") (class "Default")
      (node (ref "U1") (pin "26") (pinfunction "PB13_26") (pintype "passive"))
    )
    (net (code "82") (name "unconnected-(U1-PB14-Pad27)") (class "Default")
      (node (ref "U1") (pin "27") (pinfunction "PB14_27") (pintype "passive"))
    )
    (net (code "83") (name "unconnected-(U8-DONE-Pad5)") (class "Default")
      (node (ref "U8") (pin "5") (pinfunction "DONE_5") (pintype "passive"))
    )
  )
)
